# FTDI.net
KiCad netlist of a schematic drawn in Altium Designer
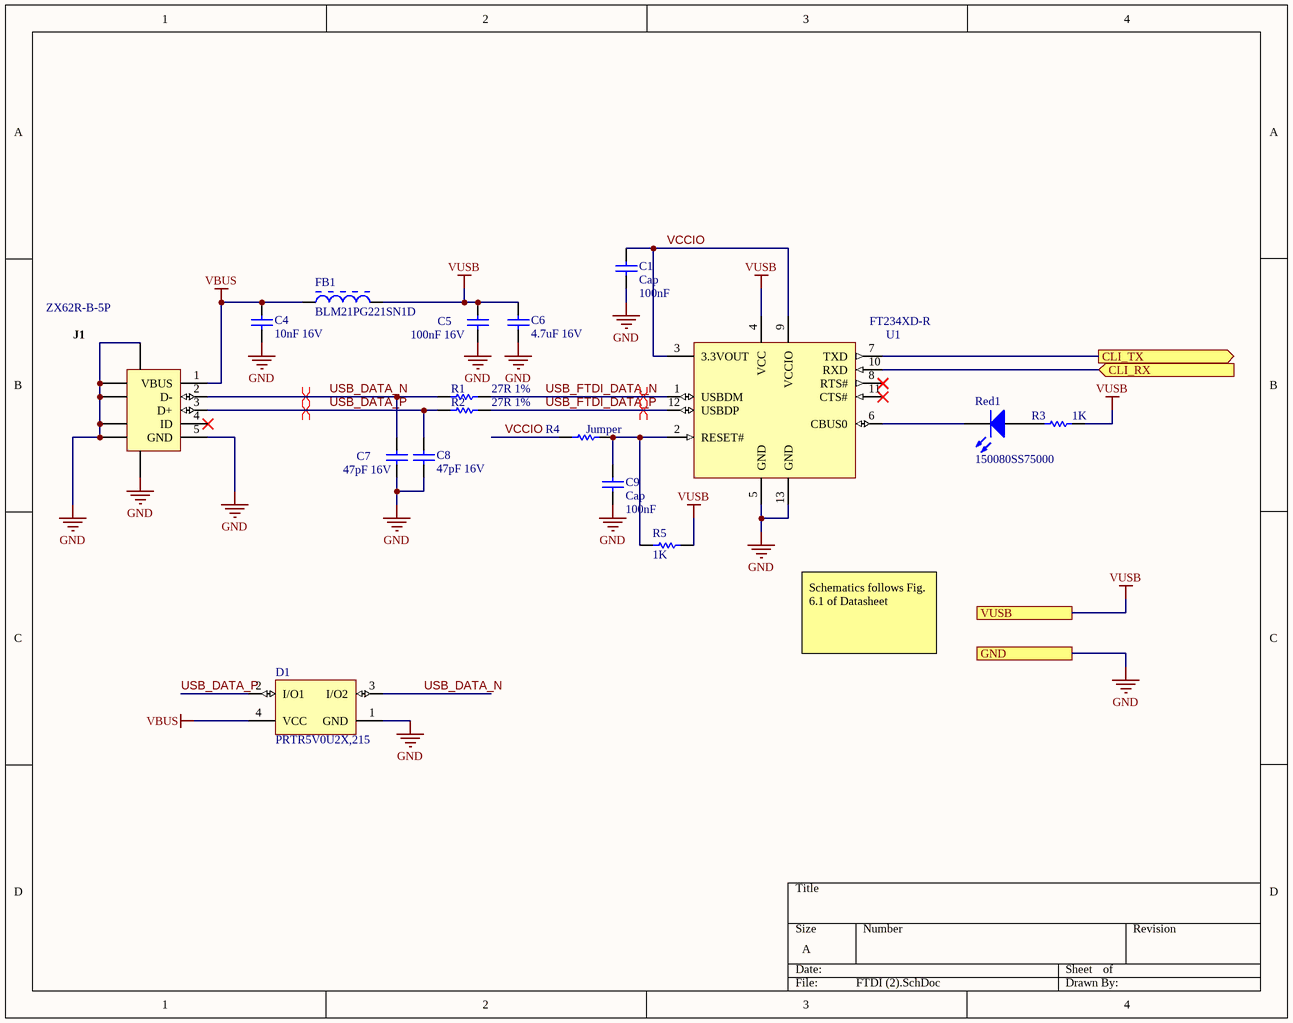
[diagram p0: FTDI (2).SchDoc]

(export (version "E")
  (design (tool "Eeschema 10.0.6"))
  (components
    (comp (ref "C1")
      (value "Cap")
      (footprint "1608[0603]")
      (description "Capacitor")
      (fields (field (name "ALTIUM_VALUE") "100nF") (field (name "PUBLISHER") "Altium Limited"))
      (libsource (lib "Miscellaneous Devices") (part "Cap"))
    )
    (comp (ref "C4")
      (value "10nF 16V")
      (footprint "CAPC0603(1608)100_L")
      (description "CAP 10nF 16V ±10% 0603 (1608 Metric) Thickness 1mm SMD")
      (fields (field (name "TOLERANCE") "Â±10%"))
      (libsource (lib "Altium Content Vault") (part "CAP"))
    )
    (comp (ref "C5")
      (value "100nF 16V")
      (footprint "CAPC0603(1608)100_N")
      (description "CAP 100nF 16V ±10% 0603 (1608 Metric) Thickness 1mm SMD")
      (fields (field (name "TOLERANCE") "Â±10%"))
      (libsource (lib "Altium Content Vault") (part "CAP"))
    )
    (comp (ref "C6")
      (value "4.7uF 16V")
      (footprint "CAPC0805(2012)145_N")
      (description "CAP 4.7uF 16V ±10% 0805 (2012 Metric) Thickness 1.45mm SMD")
      (fields (field (name "TOLERANCE") "Â±10%"))
      (libsource (lib "Altium Content Vault") (part "CAP"))
    )
    (comp (ref "C7")
      (value "47pF 16V")
      (footprint "CAPC0603(1608)100_L")
      (description "CAP 47pF 16V ±0.5pF 0603 (1608 Metric) Thickness 1mm SMD")
      (fields (field (name "TOLERANCE") "Â±0.5pF"))
      (libsource (lib "Altium Content Vault") (part "CAP"))
    )
    (comp (ref "C8")
      (value "47pF 16V")
      (footprint "CAPC0603(1608)100_L")
      (description "CAP 47pF 16V ±0.5pF 0603 (1608 Metric) Thickness 1mm SMD")
      (fields (field (name "TOLERANCE") "Â±0.5pF"))
      (libsource (lib "Altium Content Vault") (part "CAP"))
    )
    (comp (ref "C9")
      (value "Cap")
      (footprint "1608[0603]")
      (description "Capacitor")
      (fields (field (name "ALTIUM_VALUE") "100nF") (field (name "PUBLISHER") "Altium Limited"))
      (libsource (lib "Miscellaneous Devices") (part "Cap"))
    )
    (comp (ref "D1")
      (value "PRTR5V0U2X,215")
      (footprint "NXP-SOT143B-4_V")
      (fields (field (name "MANUFACTURER") "NXP Semiconductors"))
      (libsource (lib "Altium Content Vault") (part "NXP-PRTR5V0U2X,215-4"))
    )
    (comp (ref "FB1")
      (value "BLM21PG221SN1D")
      (footprint "MURA-BLM21-B20-CHIP-2_V1")
      (fields (field (name "MANUFACTURER") "Murata"))
      (libsource (lib "Altium Content Vault") (part "MURA-FB-2"))
    )
    (comp (ref "J1")
      (value "ZX62R-B-5P")
      (footprint "HIRO-ZX62R-B-5P_V")
      (description "Connector; USBMicro-B,Reverse type, SMT; 5 Position; Right Angle")
      (libsource (lib "Altium Content Vault") (part "HIRO-ZX62R-B-5P-5"))
    )
    (comp (ref "R1")
      (value "27R 1%")
      (footprint "RESC0603(1608)_N")
      (description "27R 0.1W 1% 0603 (1608 Metric)  SMD")
      (fields (field (name "TOLERANCE") "1 %") (field (name "POWER") "0.1 W"))
      (libsource (lib "Altium Content Vault") (part "RES"))
    )
    (comp (ref "R2")
      (value "27R 1%")
      (footprint "RESC0603(1608)_N")
      (description "27R 0.1W 1% 0603 (1608 Metric)  SMD")
      (fields (field (name "TOLERANCE") "1 %") (field (name "POWER") "0.1 W"))
      (libsource (lib "Altium Content Vault") (part "RES"))
    )
    (comp (ref "R3")
      (value "1K")
      (footprint "RESC0603(1608)_M")
      (description "1K 0.1W 1% 0603 (1608 Metric)  SMD")
      (fields (field (name "TOLERANCE") "1 %") (field (name "POWER") "0.1 W"))
      (libsource (lib "Altium Content Vault") (part "RES"))
    )
    (comp (ref "R4")
      (value "Jumper")
      (footprint "RESC0603(1608)_N")
      (description "Jumper 0603 (1608 Metric)")
      (fields (field (name "POWER") "None"))
      (libsource (lib "Altium Content Vault") (part "RES"))
    )
    (comp (ref "R5")
      (value "1K")
      (footprint "RESC0603(1608)_M")
      (description "1K 0.1W 1% 0603 (1608 Metric)  SMD")
      (fields (field (name "TOLERANCE") "1 %") (field (name "POWER") "0.1 W"))
      (libsource (lib "Altium Content Vault") (part "RES"))
    )
    (comp (ref "Red1")
      (value "150080SS75000")
      (footprint "0805_A")
      (description "SMD mono-color Chip LED, WL-SMCW, Super Red")
      (fields (field (name "MANUFACTURER") "Wuerth Elektronik"))
      (libsource (lib "Altium Content Vault") (part "WE-LED_K1A2-2"))
    )
    (comp (ref "U1")
      (value "FT234XD-R")
      (footprint "DFN-12_V")
      (description "FT234XD USB to BASIC UART IC, -40 to +85 degC, 12-Pin DFN, Pb-Free, Tape and Reel")
      (fields (field (name "MANUFACTURER") "FTDI"))
      (libsource (lib "Altium Content Vault") (part "CMP-0248-00027-1"))
    )
  )
  (nets
    (net (code "1") (name "/CLI_RX") (class "Default")
      (node (ref "U1") (pin "10") (pinfunction "RXD_10") (pintype "input"))
    )
    (net (code "2") (name "/CLI_TX") (class "Default")
      (node (ref "U1") (pin "7") (pinfunction "TXD_7") (pintype "output"))
    )
    (net (code "3") (name "/USB_DATA_N") (class "Default")
      (node (ref "C7") (pin "2") (pinfunction "2_2") (pintype "passive"))
      (node (ref "D1") (pin "3") (pinfunction "I/O2_3") (pintype "bidirectional"))
      (node (ref "J1") (pin "2") (pinfunction "D-_2") (pintype "bidirectional"))
      (node (ref "R1") (pin "1") (pinfunction "1_1") (pintype "passive"))
    )
    (net (code "4") (name "/USB_DATA_P") (class "Default")
      (node (ref "C8") (pin "2") (pinfunction "2_2") (pintype "passive"))
      (node (ref "D1") (pin "2") (pinfunction "I/O1_2") (pintype "bidirectional"))
      (node (ref "J1") (pin "3") (pinfunction "D+_3") (pintype "bidirectional"))
      (node (ref "R2") (pin "1") (pinfunction "1_1") (pintype "passive"))
    )
    (net (code "5") (name "/USB_FTDI_DATA_N") (class "Default")
      (node (ref "R1") (pin "2") (pinfunction "2_2") (pintype "passive"))
      (node (ref "U1") (pin "1") (pinfunction "USBDM_1") (pintype "bidirectional"))
    )
    (net (code "6") (name "/USB_FTDI_DATA_P") (class "Default")
      (node (ref "R2") (pin "2") (pinfunction "2_2") (pintype "passive"))
      (node (ref "U1") (pin "12") (pinfunction "USBDP_12") (pintype "bidirectional"))
    )
    (net (code "7") (name "/VCCIO") (class "Default")
      (node (ref "C1") (pin "2") (pinfunction "2_2") (pintype "passive"))
      (node (ref "R4") (pin "1") (pinfunction "1_1") (pintype "passive"))
      (node (ref "U1") (pin "3") (pinfunction "3.3VOUT_3") (pintype "power_in"))
      (node (ref "U1") (pin "9") (pinfunction "VCCIO_9") (pintype "power_in"))
    )
    (net (code "8") (name "GND") (class "Default")
      (node (ref "C1") (pin "1") (pinfunction "1_1") (pintype "passive"))
      (node (ref "C4") (pin "1") (pinfunction "1_1") (pintype "passive"))
      (node (ref "C5") (pin "1") (pinfunction "1_1") (pintype "passive"))
      (node (ref "C6") (pin "1") (pinfunction "1_1") (pintype "passive"))
      (node (ref "C7") (pin "1") (pinfunction "1_1") (pintype "passive"))
      (node (ref "C8") (pin "1") (pinfunction "1_1") (pintype "passive"))
      (node (ref "C9") (pin "1") (pinfunction "1_1") (pintype "passive"))
      (node (ref "D1") (pin "1") (pinfunction "GND_1") (pintype "power_in"))
      (node (ref "J1") (pin "10") (pinfunction "SHLD_10") (pintype "passive"))
      (node (ref "J1") (pin "11") (pinfunction "SHLD_11") (pintype "passive"))
      (node (ref "J1") (pin "5") (pinfunction "GND_5") (pintype "power_in"))
      (node (ref "J1") (pin "6") (pinfunction "SHLD_6") (pintype "passive"))
      (node (ref "J1") (pin "7") (pinfunction "SHLD_7") (pintype "passive"))
      (node (ref "J1") (pin "8") (pinfunction "SHLD_8") (pintype "passive"))
      (node (ref "J1") (pin "9") (pinfunction "SHLD_9") (pintype "passive"))
      (node (ref "U1") (pin "13") (pinfunction "GND_13") (pintype "power_in"))
      (node (ref "U1") (pin "5") (pinfunction "GND_5") (pintype "power_in"))
    )
    (net (code "9") (name "Net-(Red1-A)") (class "Default")
      (node (ref "R3") (pin "1") (pinfunction "1_1") (pintype "passive"))
      (node (ref "Red1") (pin "2") (pinfunction "A_2") (pintype "passive"))
    )
    (net (code "10") (name "Net-(Red1-K)") (class "Default")
      (node (ref "Red1") (pin "1") (pinfunction "K_1") (pintype "passive"))
      (node (ref "U1") (pin "6") (pinfunction "CBUS0_6") (pintype "bidirectional"))
    )
    (net (code "11") (name "Net-(U1-RESET#)") (class "Default")
      (node (ref "C9") (pin "2") (pinfunction "2_2") (pintype "passive"))
      (node (ref "R4") (pin "2") (pinfunction "2_2") (pintype "passive"))
      (node (ref "R5") (pin "2") (pinfunction "2_2") (pintype "passive"))
      (node (ref "U1") (pin "2") (pinfunction "RESET#_2") (pintype "input"))
    )
    (net (code "12") (name "VBUS") (class "Default")
      (node (ref "C4") (pin "2") (pinfunction "2_2") (pintype "passive"))
      (node (ref "D1") (pin "4") (pinfunction "VCC_4") (pintype "power_in"))
      (node (ref "FB1") (pin "1") (pinfunction "1_1") (pintype "passive"))
      (node (ref "J1") (pin "1") (pinfunction "VBUS_1") (pintype "power_in"))
    )
    (net (code "13") (name "VUSB") (class "Default")
      (node (ref "C5") (pin "2") (pinfunction "2_2") (pintype "passive"))
      (node (ref "C6") (pin "2") (pinfunction "2_2") (pintype "passive"))
      (node (ref "FB1") (pin "2") (pinfunction "2_2") (pintype "passive"))
      (node (ref "R3") (pin "2") (pinfunction "2_2") (pintype "passive"))
      (node (ref "R5") (pin "1") (pinfunction "1_1") (pintype "passive"))
      (node (ref "U1") (pin "4") (pinfunction "VCC_4") (pintype "power_in"))
    )
    (net (code "14") (name "unconnected-(J1-ID-Pad4)") (class "Default")
      (node (ref "J1") (pin "4") (pinfunction "ID_4") (pintype "passive+no_connect"))
    )
    (net (code "15") (name "unconnected-(U1-CTS#-Pad11)") (class "Default")
      (node (ref "U1") (pin "11") (pinfunction "CTS#_11") (pintype "input+no_connect"))
    )
    (net (code "16") (name "unconnected-(U1-RTS#-Pad8)") (class "Default")
      (node (ref "U1") (pin "8") (pinfunction "RTS#_8") (pintype "output+no_connect"))
    )
  )
)
